# 2017_CHECK_UP_LED.net
KiCad netlist of a schematic drawn in Altium Designer
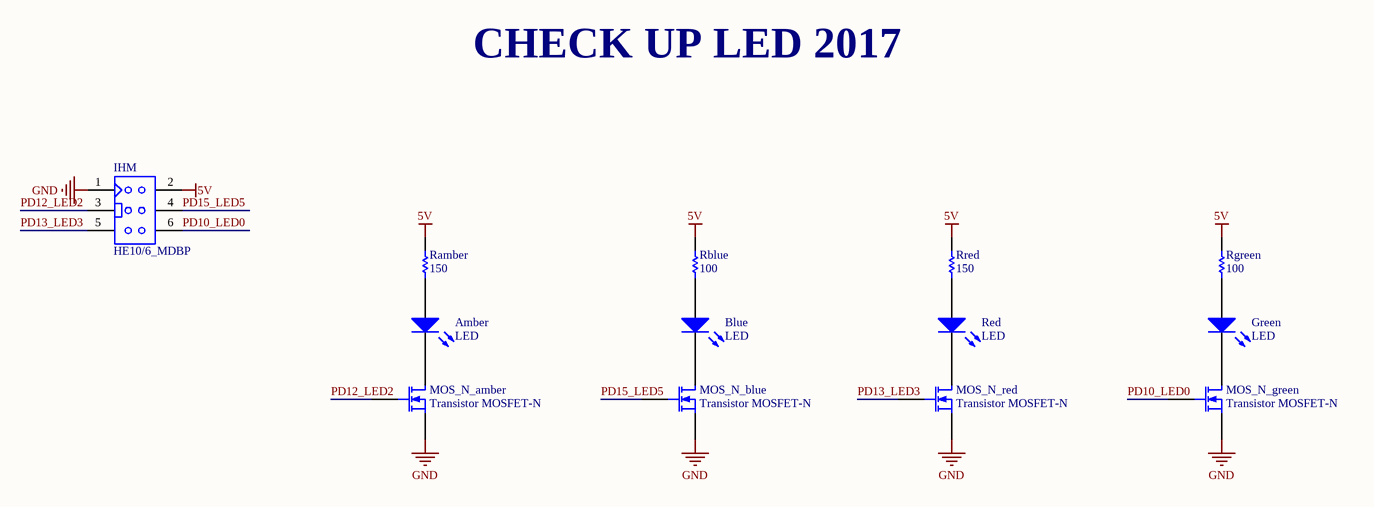
[diagram p0: 2017_CHECK UP LED.SchDoc]

(export (version "E")
  (design (tool "Eeschema 10.0.6"))
  (components
    (comp (ref "Amber")
      (value "LED")
      (footprint "LED_1206")
      (description "Typical LED")
      (fields (field (name "PUBLISHER") "Altium Limited"))
      (libsource (lib "_ROBOT") (part "LED"))
    )
    (comp (ref "Blue")
      (value "LED")
      (footprint "LED_1206")
      (description "Typical LED")
      (fields (field (name "PUBLISHER") "Altium Limited"))
      (libsource (lib "_ROBOT") (part "LED"))
    )
    (comp (ref "Green")
      (value "LED")
      (footprint "LED_1206")
      (description "Typical LED")
      (fields (field (name "PUBLISHER") "Altium Limited"))
      (libsource (lib "_ROBOT") (part "LED"))
    )
    (comp (ref "IHM")
      (value "HE10/6_MALE_DROIT_BAS PROFIL")
      (footprint "HE10/6_M_D_BP")
      (description "EMBASE HE10/6 MALE DROIT BAS PROFIL")
      (fields (field (name "TYPE") "HE10/6_MDBP"))
      (libsource (lib "connecteurs") (part "HE10/6_MALE_DROIT_BAS PROFIL"))
    )
    (comp (ref "MOS_N_amber")
      (value "Transistor MOSFET-N")
      (footprint "SOT23-3N")
      (description "N-Channel MOSFET")
      (fields (field (name "PUBLISHER") "Altium Limited"))
      (libsource (lib "_ROBOT") (part "Transistor MOSFET-N"))
    )
    (comp (ref "MOS_N_blue")
      (value "Transistor MOSFET-N")
      (footprint "SOT23-3N")
      (description "N-Channel MOSFET")
      (fields (field (name "PUBLISHER") "Altium Limited"))
      (libsource (lib "_ROBOT") (part "Transistor MOSFET-N"))
    )
    (comp (ref "MOS_N_green")
      (value "Transistor MOSFET-N")
      (footprint "SOT23-3N")
      (description "N-Channel MOSFET")
      (fields (field (name "PUBLISHER") "Altium Limited"))
      (libsource (lib "_ROBOT") (part "Transistor MOSFET-N"))
    )
    (comp (ref "MOS_N_red")
      (value "Transistor MOSFET-N")
      (footprint "SOT23-3N")
      (description "N-Channel MOSFET")
      (fields (field (name "PUBLISHER") "Altium Limited"))
      (libsource (lib "_ROBOT") (part "Transistor MOSFET-N"))
    )
    (comp (ref "Ramber")
      (value "150")
      (footprint "R1206_N")
      (description "Resistor")
      (fields (field (name "PUBLISHER") "Altium Limited"))
      (libsource (lib "_ROBOT") (part "Resistor"))
    )
    (comp (ref "Rblue")
      (value "100")
      (footprint "R1206_N")
      (description "Resistor")
      (fields (field (name "PUBLISHER") "Altium Limited"))
      (libsource (lib "_ROBOT") (part "Resistor"))
    )
    (comp (ref "Red")
      (value "LED")
      (footprint "LED_1206")
      (description "Typical LED")
      (fields (field (name "PUBLISHER") "Altium Limited"))
      (libsource (lib "_ROBOT") (part "LED"))
    )
    (comp (ref "Rgreen")
      (value "100")
      (footprint "R1206_N")
      (description "Resistor")
      (fields (field (name "PUBLISHER") "Altium Limited"))
      (libsource (lib "_ROBOT") (part "Resistor"))
    )
    (comp (ref "Rred")
      (value "150")
      (footprint "R1206_N")
      (description "Resistor")
      (fields (field (name "PUBLISHER") "Altium Limited"))
      (libsource (lib "_ROBOT") (part "Resistor"))
    )
  )
  (nets
    (net (code "1") (name "/PD10_LED0") (class "Default")
      (node (ref "IHM") (pin "6") (pinfunction "6_6") (pintype "passive"))
      (node (ref "MOS_N_green") (pin "1") (pinfunction "G_1") (pintype "passive"))
    )
    (net (code "2") (name "/PD12_LED2") (class "Default")
      (node (ref "IHM") (pin "3") (pinfunction "3_3") (pintype "passive"))
      (node (ref "MOS_N_amber") (pin "1") (pinfunction "G_1") (pintype "passive"))
    )
    (net (code "3") (name "/PD13_LED3") (class "Default")
      (node (ref "IHM") (pin "5") (pinfunction "5_5") (pintype "passive"))
      (node (ref "MOS_N_red") (pin "1") (pinfunction "G_1") (pintype "passive"))
    )
    (net (code "4") (name "/PD15_LED5") (class "Default")
      (node (ref "IHM") (pin "4") (pinfunction "4_4") (pintype "passive"))
      (node (ref "MOS_N_blue") (pin "1") (pinfunction "G_1") (pintype "passive"))
    )
    (net (code "5") (name "5V") (class "Default")
      (node (ref "IHM") (pin "2") (pinfunction "2_2") (pintype "passive"))
      (node (ref "Ramber") (pin "2") (pinfunction "2_2") (pintype "passive"))
      (node (ref "Rblue") (pin "2") (pinfunction "2_2") (pintype "passive"))
      (node (ref "Rgreen") (pin "2") (pinfunction "2_2") (pintype "passive"))
      (node (ref "Rred") (pin "2") (pinfunction "2_2") (pintype "passive"))
    )
    (net (code "6") (name "GND") (class "Default")
      (node (ref "IHM") (pin "1") (pinfunction "1_1") (pintype "passive"))
      (node (ref "MOS_N_amber") (pin "2") (pinfunction "S_2") (pintype "passive"))
      (node (ref "MOS_N_blue") (pin "2") (pinfunction "S_2") (pintype "passive"))
      (node (ref "MOS_N_green") (pin "2") (pinfunction "S_2") (pintype "passive"))
      (node (ref "MOS_N_red") (pin "2") (pinfunction "S_2") (pintype "passive"))
    )
    (net (code "7") (name "Net-(Amber-A)") (class "Default")
      (node (ref "Amber") (pin "1") (pinfunction "A_1") (pintype "passive"))
      (node (ref "Ramber") (pin "1") (pinfunction "1_1") (pintype "passive"))
    )
    (net (code "8") (name "Net-(Amber-K)") (class "Default")
      (node (ref "Amber") (pin "2") (pinfunction "K_2") (pintype "passive"))
      (node (ref "MOS_N_amber") (pin "3") (pinfunction "D_3") (pintype "passive"))
    )
    (net (code "9") (name "Net-(Blue-A)") (class "Default")
      (node (ref "Blue") (pin "1") (pinfunction "A_1") (pintype "passive"))
      (node (ref "Rblue") (pin "1") (pinfunction "1_1") (pintype "passive"))
    )
    (net (code "10") (name "Net-(Blue-K)") (class "Default")
      (node (ref "Blue") (pin "2") (pinfunction "K_2") (pintype "passive"))
      (node (ref "MOS_N_blue") (pin "3") (pinfunction "D_3") (pintype "passive"))
    )
    (net (code "11") (name "Net-(Green-A)") (class "Default")
      (node (ref "Green") (pin "1") (pinfunction "A_1") (pintype "passive"))
      (node (ref "Rgreen") (pin "1") (pinfunction "1_1") (pintype "passive"))
    )
    (net (code "12") (name "Net-(Green-K)") (class "Default")
      (node (ref "Green") (pin "2") (pinfunction "K_2") (pintype "passive"))
      (node (ref "MOS_N_green") (pin "3") (pinfunction "D_3") (pintype "passive"))
    )
    (net (code "13") (name "Net-(MOS_N_red-D)") (class "Default")
      (node (ref "MOS_N_red") (pin "3") (pinfunction "D_3") (pintype "passive"))
      (node (ref "Red") (pin "2") (pinfunction "K_2") (pintype "passive"))
    )
    (net (code "14") (name "Net-(Red-A)") (class "Default")
      (node (ref "Red") (pin "1") (pinfunction "A_1") (pintype "passive"))
      (node (ref "Rred") (pin "1") (pinfunction "1_1") (pintype "passive"))
    )
  )
)
